# Board_Tanggal_v2.net
KiCad netlist of a schematic drawn in EAGLE
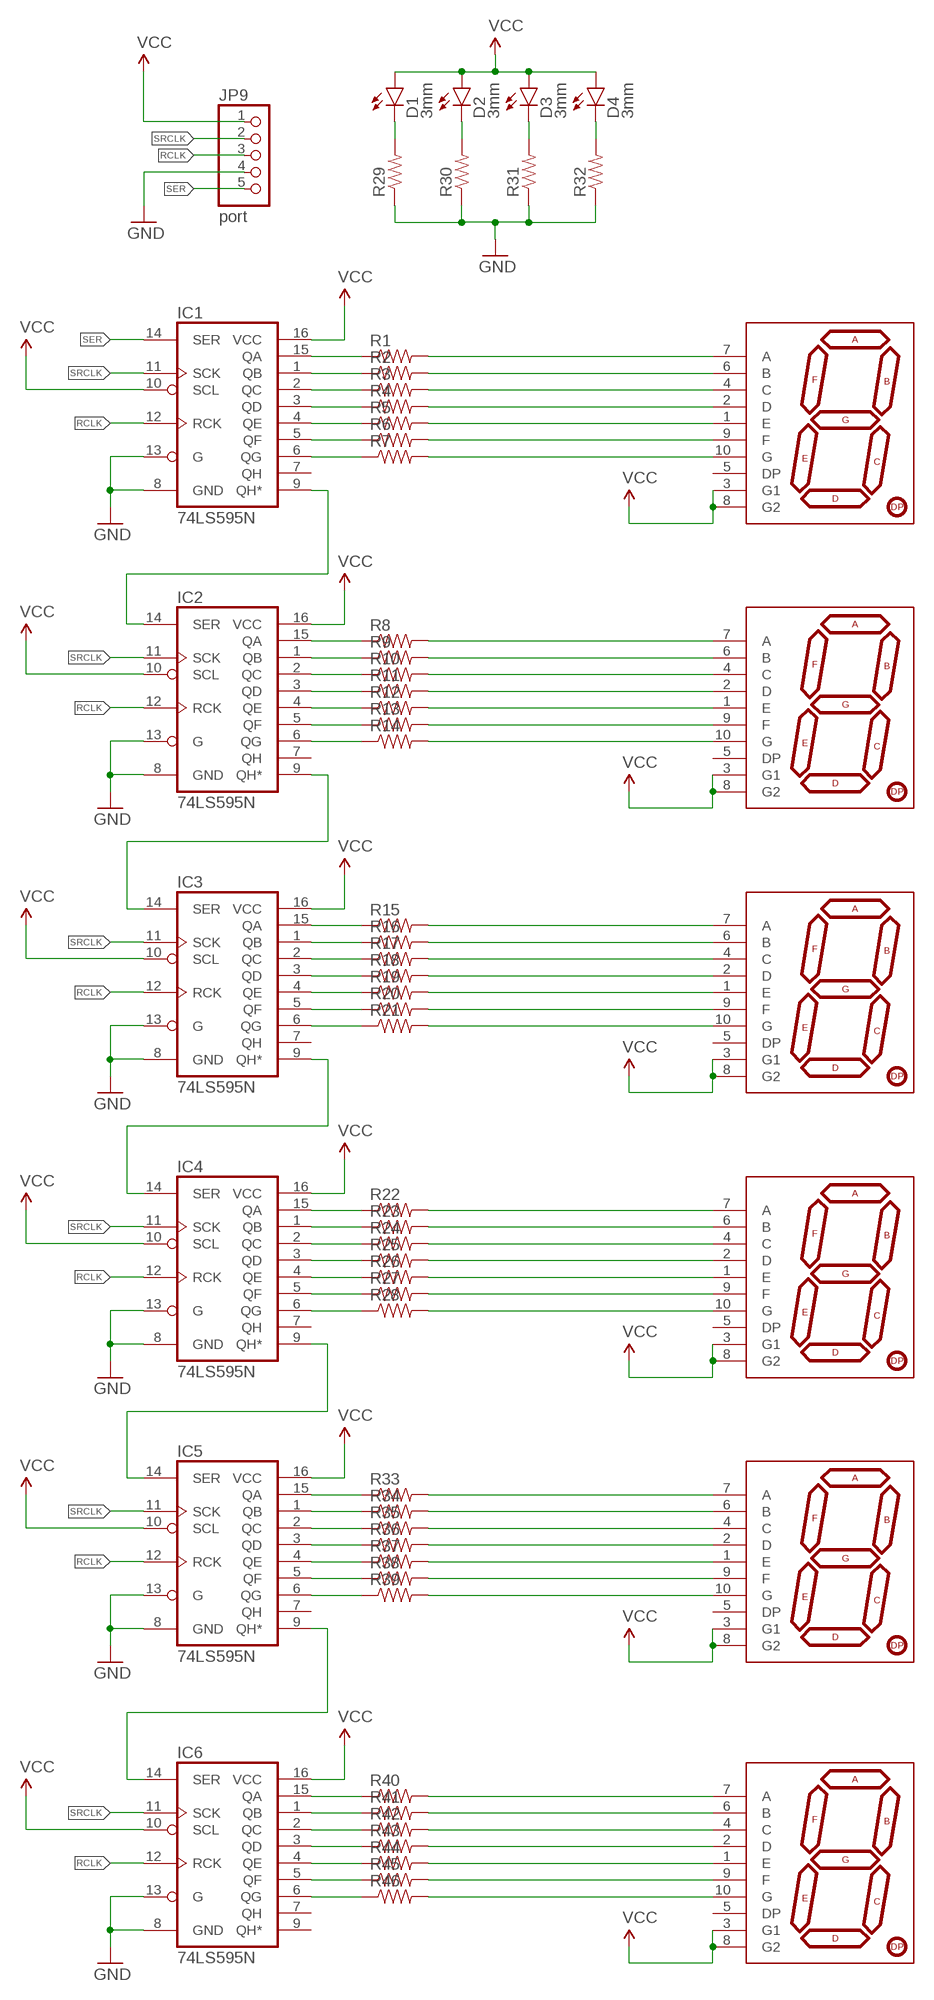
[diagram p0: schematic, sheet 1]

(export (version "E")
  (design (tool "Eeschema 10.0.6"))
  (components
    (comp (ref "D1")
      (value "3mm")
      (footprint "eagle-import:LED3MM")
      (libsource (lib "eagle-import") (part "LED3MM"))
    )
    (comp (ref "D2")
      (value "3mm")
      (footprint "eagle-import:LED3MM")
      (libsource (lib "eagle-import") (part "LED3MM"))
    )
    (comp (ref "D3")
      (value "3mm")
      (footprint "eagle-import:LED3MM")
      (libsource (lib "eagle-import") (part "LED3MM"))
    )
    (comp (ref "D4")
      (value "3mm")
      (footprint "eagle-import:LED3MM")
      (libsource (lib "eagle-import") (part "LED3MM"))
    )
    (comp (ref "IC1")
      (value "74LS595N")
      (footprint "eagle-import:DIL16")
      (libsource (lib "eagle-import") (part "74595NLS"))
    )
    (comp (ref "IC2")
      (value "74LS595N")
      (footprint "eagle-import:DIL16")
      (libsource (lib "eagle-import") (part "74595NLS"))
    )
    (comp (ref "IC3")
      (value "74LS595N")
      (footprint "eagle-import:DIL16")
      (libsource (lib "eagle-import") (part "74595NLS"))
    )
    (comp (ref "IC4")
      (value "74LS595N")
      (footprint "eagle-import:DIL16")
      (libsource (lib "eagle-import") (part "74595NLS"))
    )
    (comp (ref "IC5")
      (value "74LS595N")
      (footprint "eagle-import:DIL16")
      (libsource (lib "eagle-import") (part "74595NLS"))
    )
    (comp (ref "IC6")
      (value "74LS595N")
      (footprint "eagle-import:DIL16")
      (libsource (lib "eagle-import") (part "74595NLS"))
    )
    (comp (ref "JP9")
      (value "port")
      (footprint "eagle-import:1X05")
      (libsource (lib "eagle-import") (part "PINHD-1X5"))
    )
    (comp (ref "R1")
      (value "RESISTORPTH-1/4W")
      (footprint "eagle-import:AXIAL-0.4")
      (libsource (lib "eagle-import") (part "RESISTORPTH-1/4W"))
    )
    (comp (ref "R2")
      (value "RESISTORPTH-1/4W")
      (footprint "eagle-import:AXIAL-0.4")
      (libsource (lib "eagle-import") (part "RESISTORPTH-1/4W"))
    )
    (comp (ref "R3")
      (value "RESISTORPTH-1/4W")
      (footprint "eagle-import:AXIAL-0.4")
      (libsource (lib "eagle-import") (part "RESISTORPTH-1/4W"))
    )
    (comp (ref "R4")
      (value "RESISTORPTH-1/4W")
      (footprint "eagle-import:AXIAL-0.4")
      (libsource (lib "eagle-import") (part "RESISTORPTH-1/4W"))
    )
    (comp (ref "R5")
      (value "RESISTORPTH-1/4W")
      (footprint "eagle-import:AXIAL-0.4")
      (libsource (lib "eagle-import") (part "RESISTORPTH-1/4W"))
    )
    (comp (ref "R6")
      (value "RESISTORPTH-1/4W")
      (footprint "eagle-import:AXIAL-0.4")
      (libsource (lib "eagle-import") (part "RESISTORPTH-1/4W"))
    )
    (comp (ref "R7")
      (value "RESISTORPTH-1/4W")
      (footprint "eagle-import:AXIAL-0.4")
      (libsource (lib "eagle-import") (part "RESISTORPTH-1/4W"))
    )
    (comp (ref "R8")
      (value "RESISTORPTH-1/4W")
      (footprint "eagle-import:AXIAL-0.4")
      (libsource (lib "eagle-import") (part "RESISTORPTH-1/4W"))
    )
    (comp (ref "R9")
      (value "RESISTORPTH-1/4W")
      (footprint "eagle-import:AXIAL-0.4")
      (libsource (lib "eagle-import") (part "RESISTORPTH-1/4W"))
    )
    (comp (ref "R10")
      (value "RESISTORPTH-1/4W")
      (footprint "eagle-import:AXIAL-0.4")
      (libsource (lib "eagle-import") (part "RESISTORPTH-1/4W"))
    )
    (comp (ref "R11")
      (value "RESISTORPTH-1/4W")
      (footprint "eagle-import:AXIAL-0.4")
      (libsource (lib "eagle-import") (part "RESISTORPTH-1/4W"))
    )
    (comp (ref "R12")
      (value "RESISTORPTH-1/4W")
      (footprint "eagle-import:AXIAL-0.4")
      (libsource (lib "eagle-import") (part "RESISTORPTH-1/4W"))
    )
    (comp (ref "R13")
      (value "RESISTORPTH-1/4W")
      (footprint "eagle-import:AXIAL-0.4")
      (libsource (lib "eagle-import") (part "RESISTORPTH-1/4W"))
    )
    (comp (ref "R14")
      (value "RESISTORPTH-1/4W")
      (footprint "eagle-import:AXIAL-0.4")
      (libsource (lib "eagle-import") (part "RESISTORPTH-1/4W"))
    )
    (comp (ref "R15")
      (value "RESISTORPTH-1/4W")
      (footprint "eagle-import:AXIAL-0.4")
      (libsource (lib "eagle-import") (part "RESISTORPTH-1/4W"))
    )
    (comp (ref "R16")
      (value "RESISTORPTH-1/4W")
      (footprint "eagle-import:AXIAL-0.4")
      (libsource (lib "eagle-import") (part "RESISTORPTH-1/4W"))
    )
    (comp (ref "R17")
      (value "RESISTORPTH-1/4W")
      (footprint "eagle-import:AXIAL-0.4")
      (libsource (lib "eagle-import") (part "RESISTORPTH-1/4W"))
    )
    (comp (ref "R18")
      (value "RESISTORPTH-1/4W")
      (footprint "eagle-import:AXIAL-0.4")
      (libsource (lib "eagle-import") (part "RESISTORPTH-1/4W"))
    )
    (comp (ref "R19")
      (value "RESISTORPTH-1/4W")
      (footprint "eagle-import:AXIAL-0.4")
      (libsource (lib "eagle-import") (part "RESISTORPTH-1/4W"))
    )
    (comp (ref "R20")
      (value "RESISTORPTH-1/4W")
      (footprint "eagle-import:AXIAL-0.4")
      (libsource (lib "eagle-import") (part "RESISTORPTH-1/4W"))
    )
    (comp (ref "R21")
      (value "RESISTORPTH-1/4W")
      (footprint "eagle-import:AXIAL-0.4")
      (libsource (lib "eagle-import") (part "RESISTORPTH-1/4W"))
    )
    (comp (ref "R22")
      (value "RESISTORPTH-1/4W")
      (footprint "eagle-import:AXIAL-0.4")
      (libsource (lib "eagle-import") (part "RESISTORPTH-1/4W"))
    )
    (comp (ref "R23")
      (value "RESISTORPTH-1/4W")
      (footprint "eagle-import:AXIAL-0.4")
      (libsource (lib "eagle-import") (part "RESISTORPTH-1/4W"))
    )
    (comp (ref "R24")
      (value "RESISTORPTH-1/4W")
      (footprint "eagle-import:AXIAL-0.4")
      (libsource (lib "eagle-import") (part "RESISTORPTH-1/4W"))
    )
    (comp (ref "R25")
      (value "RESISTORPTH-1/4W")
      (footprint "eagle-import:AXIAL-0.4")
      (libsource (lib "eagle-import") (part "RESISTORPTH-1/4W"))
    )
    (comp (ref "R26")
      (value "RESISTORPTH-1/4W")
      (footprint "eagle-import:AXIAL-0.4")
      (libsource (lib "eagle-import") (part "RESISTORPTH-1/4W"))
    )
    (comp (ref "R27")
      (value "RESISTORPTH-1/4W")
      (footprint "eagle-import:AXIAL-0.4")
      (libsource (lib "eagle-import") (part "RESISTORPTH-1/4W"))
    )
    (comp (ref "R28")
      (value "RESISTORPTH-1/4W")
      (footprint "eagle-import:AXIAL-0.4")
      (libsource (lib "eagle-import") (part "RESISTORPTH-1/4W"))
    )
    (comp (ref "R29")
      (value "RESISTORPTH-1/4W")
      (footprint "eagle-import:AXIAL-0.4")
      (libsource (lib "eagle-import") (part "RESISTORPTH-1/4W"))
    )
    (comp (ref "R30")
      (value "RESISTORPTH-1/4W")
      (footprint "eagle-import:AXIAL-0.4")
      (libsource (lib "eagle-import") (part "RESISTORPTH-1/4W"))
    )
    (comp (ref "R31")
      (value "RESISTORPTH-1/4W")
      (footprint "eagle-import:AXIAL-0.4")
      (libsource (lib "eagle-import") (part "RESISTORPTH-1/4W"))
    )
    (comp (ref "R32")
      (value "RESISTORPTH-1/4W")
      (footprint "eagle-import:AXIAL-0.4")
      (libsource (lib "eagle-import") (part "RESISTORPTH-1/4W"))
    )
    (comp (ref "R33")
      (value "RESISTORPTH-1/4W")
      (footprint "eagle-import:AXIAL-0.4")
      (libsource (lib "eagle-import") (part "RESISTORPTH-1/4W"))
    )
    (comp (ref "R34")
      (value "RESISTORPTH-1/4W")
      (footprint "eagle-import:AXIAL-0.4")
      (libsource (lib "eagle-import") (part "RESISTORPTH-1/4W"))
    )
    (comp (ref "R35")
      (value "RESISTORPTH-1/4W")
      (footprint "eagle-import:AXIAL-0.4")
      (libsource (lib "eagle-import") (part "RESISTORPTH-1/4W"))
    )
    (comp (ref "R36")
      (value "RESISTORPTH-1/4W")
      (footprint "eagle-import:AXIAL-0.4")
      (libsource (lib "eagle-import") (part "RESISTORPTH-1/4W"))
    )
    (comp (ref "R37")
      (value "RESISTORPTH-1/4W")
      (footprint "eagle-import:AXIAL-0.4")
      (libsource (lib "eagle-import") (part "RESISTORPTH-1/4W"))
    )
    (comp (ref "R38")
      (value "RESISTORPTH-1/4W")
      (footprint "eagle-import:AXIAL-0.4")
      (libsource (lib "eagle-import") (part "RESISTORPTH-1/4W"))
    )
    (comp (ref "R39")
      (value "RESISTORPTH-1/4W")
      (footprint "eagle-import:AXIAL-0.4")
      (libsource (lib "eagle-import") (part "RESISTORPTH-1/4W"))
    )
    (comp (ref "R40")
      (value "RESISTORPTH-1/4W")
      (footprint "eagle-import:AXIAL-0.4")
      (libsource (lib "eagle-import") (part "RESISTORPTH-1/4W"))
    )
    (comp (ref "R41")
      (value "RESISTORPTH-1/4W")
      (footprint "eagle-import:AXIAL-0.4")
      (libsource (lib "eagle-import") (part "RESISTORPTH-1/4W"))
    )
    (comp (ref "R42")
      (value "RESISTORPTH-1/4W")
      (footprint "eagle-import:AXIAL-0.4")
      (libsource (lib "eagle-import") (part "RESISTORPTH-1/4W"))
    )
    (comp (ref "R43")
      (value "RESISTORPTH-1/4W")
      (footprint "eagle-import:AXIAL-0.4")
      (libsource (lib "eagle-import") (part "RESISTORPTH-1/4W"))
    )
    (comp (ref "R44")
      (value "RESISTORPTH-1/4W")
      (footprint "eagle-import:AXIAL-0.4")
      (libsource (lib "eagle-import") (part "RESISTORPTH-1/4W"))
    )
    (comp (ref "R45")
      (value "RESISTORPTH-1/4W")
      (footprint "eagle-import:AXIAL-0.4")
      (libsource (lib "eagle-import") (part "RESISTORPTH-1/4W"))
    )
    (comp (ref "R46")
      (value "RESISTORPTH-1/4W")
      (footprint "eagle-import:AXIAL-0.4")
      (libsource (lib "eagle-import") (part "RESISTORPTH-1/4W"))
    )
    (comp (ref "U$1")
      (value "7-SEGMENT-DISPLAY-1\"-REDEZ")
      (footprint "eagle-import:7-SEGMENT-1_PTH-EZ")
      (libsource (lib "eagle-import") (part "7-SEGMENT-DISPLAY-1{dblquote}-REDEZ"))
    )
    (comp (ref "U$2")
      (value "7-SEGMENT-DISPLAY-1\"-REDEZ")
      (footprint "eagle-import:7-SEGMENT-1_PTH-EZ")
      (libsource (lib "eagle-import") (part "7-SEGMENT-DISPLAY-1{dblquote}-REDEZ"))
    )
    (comp (ref "U$3")
      (value "7-SEGMENT-DISPLAY-1\"-REDEZ")
      (footprint "eagle-import:7-SEGMENT-1_PTH-EZ")
      (libsource (lib "eagle-import") (part "7-SEGMENT-DISPLAY-1{dblquote}-REDEZ"))
    )
    (comp (ref "U$4")
      (value "7-SEGMENT-DISPLAY-1\"-REDEZ")
      (footprint "eagle-import:7-SEGMENT-1_PTH-EZ")
      (libsource (lib "eagle-import") (part "7-SEGMENT-DISPLAY-1{dblquote}-REDEZ"))
    )
    (comp (ref "U$5")
      (value "7-SEGMENT-DISPLAY-1\"-REDEZ")
      (footprint "eagle-import:7-SEGMENT-1_PTH-EZ")
      (libsource (lib "eagle-import") (part "7-SEGMENT-DISPLAY-1{dblquote}-REDEZ"))
    )
    (comp (ref "U$6")
      (value "7-SEGMENT-DISPLAY-1\"-REDEZ")
      (footprint "eagle-import:7-SEGMENT-1_PTH-EZ")
      (libsource (lib "eagle-import") (part "7-SEGMENT-DISPLAY-1{dblquote}-REDEZ"))
    )
  )
  (nets
    (net (code "1") (name "GND") (class "Default")
      (node (ref "IC1") (pin "13") (pinfunction "G_13") (pintype "input"))
      (node (ref "IC1") (pin "8") (pinfunction "GND_8") (pintype "power_in"))
      (node (ref "IC2") (pin "13") (pinfunction "G_13") (pintype "input"))
      (node (ref "IC2") (pin "8") (pinfunction "GND_8") (pintype "power_in"))
      (node (ref "IC3") (pin "13") (pinfunction "G_13") (pintype "input"))
      (node (ref "IC3") (pin "8") (pinfunction "GND_8") (pintype "power_in"))
      (node (ref "IC4") (pin "13") (pinfunction "G_13") (pintype "input"))
      (node (ref "IC4") (pin "8") (pinfunction "GND_8") (pintype "power_in"))
      (node (ref "IC5") (pin "13") (pinfunction "G_13") (pintype "input"))
      (node (ref "IC5") (pin "8") (pinfunction "GND_8") (pintype "power_in"))
      (node (ref "IC6") (pin "13") (pinfunction "G_13") (pintype "input"))
      (node (ref "IC6") (pin "8") (pinfunction "GND_8") (pintype "power_in"))
      (node (ref "JP9") (pin "4") (pinfunction "4_4") (pintype "passive"))
      (node (ref "R29") (pin "P$1") (pinfunction "1_P$1") (pintype "passive"))
      (node (ref "R30") (pin "P$1") (pinfunction "1_P$1") (pintype "passive"))
      (node (ref "R31") (pin "P$1") (pinfunction "1_P$1") (pintype "passive"))
      (node (ref "R32") (pin "P$1") (pinfunction "1_P$1") (pintype "passive"))
    )
    (net (code "2") (name "Net-(D1-C)") (class "Default")
      (node (ref "D1") (pin "K") (pinfunction "C_K") (pintype "passive"))
      (node (ref "R29") (pin "P$2") (pinfunction "2_P$2") (pintype "passive"))
    )
    (net (code "3") (name "Net-(D2-C)") (class "Default")
      (node (ref "D2") (pin "K") (pinfunction "C_K") (pintype "passive"))
      (node (ref "R30") (pin "P$2") (pinfunction "2_P$2") (pintype "passive"))
    )
    (net (code "4") (name "Net-(D3-C)") (class "Default")
      (node (ref "D3") (pin "K") (pinfunction "C_K") (pintype "passive"))
      (node (ref "R31") (pin "P$2") (pinfunction "2_P$2") (pintype "passive"))
    )
    (net (code "5") (name "Net-(D4-C)") (class "Default")
      (node (ref "D4") (pin "K") (pinfunction "C_K") (pintype "passive"))
      (node (ref "R32") (pin "P$2") (pinfunction "2_P$2") (pintype "passive"))
    )
    (net (code "6") (name "Net-(IC1-QA)") (class "Default")
      (node (ref "IC1") (pin "15") (pinfunction "QA_15") (pintype "tri_state"))
      (node (ref "R1") (pin "P$1") (pinfunction "1_P$1") (pintype "passive"))
    )
    (net (code "7") (name "Net-(IC1-QB)") (class "Default")
      (node (ref "IC1") (pin "1") (pinfunction "QB_1") (pintype "tri_state"))
      (node (ref "R2") (pin "P$1") (pinfunction "1_P$1") (pintype "passive"))
    )
    (net (code "8") (name "Net-(IC1-QC)") (class "Default")
      (node (ref "IC1") (pin "2") (pinfunction "QC_2") (pintype "tri_state"))
      (node (ref "R3") (pin "P$1") (pinfunction "1_P$1") (pintype "passive"))
    )
    (net (code "9") (name "Net-(IC1-QD)") (class "Default")
      (node (ref "IC1") (pin "3") (pinfunction "QD_3") (pintype "tri_state"))
      (node (ref "R4") (pin "P$1") (pinfunction "1_P$1") (pintype "passive"))
    )
    (net (code "10") (name "Net-(IC1-QE)") (class "Default")
      (node (ref "IC1") (pin "4") (pinfunction "QE_4") (pintype "tri_state"))
      (node (ref "R5") (pin "P$1") (pinfunction "1_P$1") (pintype "passive"))
    )
    (net (code "11") (name "Net-(IC1-QF)") (class "Default")
      (node (ref "IC1") (pin "5") (pinfunction "QF_5") (pintype "tri_state"))
      (node (ref "R6") (pin "P$1") (pinfunction "1_P$1") (pintype "passive"))
    )
    (net (code "12") (name "Net-(IC1-QG)") (class "Default")
      (node (ref "IC1") (pin "6") (pinfunction "QG_6") (pintype "tri_state"))
      (node (ref "R7") (pin "P$1") (pinfunction "1_P$1") (pintype "passive"))
    )
    (net (code "13") (name "Net-(IC1-QH*)") (class "Default")
      (node (ref "IC1") (pin "9") (pinfunction "QH*_9") (pintype "tri_state"))
      (node (ref "IC2") (pin "14") (pinfunction "SER_14") (pintype "input"))
    )
    (net (code "14") (name "Net-(IC2-QA)") (class "Default")
      (node (ref "IC2") (pin "15") (pinfunction "QA_15") (pintype "tri_state"))
      (node (ref "R8") (pin "P$1") (pinfunction "1_P$1") (pintype "passive"))
    )
    (net (code "15") (name "Net-(IC2-QB)") (class "Default")
      (node (ref "IC2") (pin "1") (pinfunction "QB_1") (pintype "tri_state"))
      (node (ref "R9") (pin "P$1") (pinfunction "1_P$1") (pintype "passive"))
    )
    (net (code "16") (name "Net-(IC2-QC)") (class "Default")
      (node (ref "IC2") (pin "2") (pinfunction "QC_2") (pintype "tri_state"))
      (node (ref "R10") (pin "P$1") (pinfunction "1_P$1") (pintype "passive"))
    )
    (net (code "17") (name "Net-(IC2-QD)") (class "Default")
      (node (ref "IC2") (pin "3") (pinfunction "QD_3") (pintype "tri_state"))
      (node (ref "R11") (pin "P$1") (pinfunction "1_P$1") (pintype "passive"))
    )
    (net (code "18") (name "Net-(IC2-QE)") (class "Default")
      (node (ref "IC2") (pin "4") (pinfunction "QE_4") (pintype "tri_state"))
      (node (ref "R12") (pin "P$1") (pinfunction "1_P$1") (pintype "passive"))
    )
    (net (code "19") (name "Net-(IC2-QF)") (class "Default")
      (node (ref "IC2") (pin "5") (pinfunction "QF_5") (pintype "tri_state"))
      (node (ref "R13") (pin "P$1") (pinfunction "1_P$1") (pintype "passive"))
    )
    (net (code "20") (name "Net-(IC2-QG)") (class "Default")
      (node (ref "IC2") (pin "6") (pinfunction "QG_6") (pintype "tri_state"))
      (node (ref "R14") (pin "P$1") (pinfunction "1_P$1") (pintype "passive"))
    )
    (net (code "21") (name "Net-(IC2-QH*)") (class "Default")
      (node (ref "IC2") (pin "9") (pinfunction "QH*_9") (pintype "tri_state"))
      (node (ref "IC3") (pin "14") (pinfunction "SER_14") (pintype "input"))
    )
    (net (code "22") (name "Net-(IC3-QA)") (class "Default")
      (node (ref "IC3") (pin "15") (pinfunction "QA_15") (pintype "tri_state"))
      (node (ref "R15") (pin "P$1") (pinfunction "1_P$1") (pintype "passive"))
    )
    (net (code "23") (name "Net-(IC3-QB)") (class "Default")
      (node (ref "IC3") (pin "1") (pinfunction "QB_1") (pintype "tri_state"))
      (node (ref "R16") (pin "P$1") (pinfunction "1_P$1") (pintype "passive"))
    )
    (net (code "24") (name "Net-(IC3-QC)") (class "Default")
      (node (ref "IC3") (pin "2") (pinfunction "QC_2") (pintype "tri_state"))
      (node (ref "R17") (pin "P$1") (pinfunction "1_P$1") (pintype "passive"))
    )
    (net (code "25") (name "Net-(IC3-QD)") (class "Default")
      (node (ref "IC3") (pin "3") (pinfunction "QD_3") (pintype "tri_state"))
      (node (ref "R18") (pin "P$1") (pinfunction "1_P$1") (pintype "passive"))
    )
    (net (code "26") (name "Net-(IC3-QE)") (class "Default")
      (node (ref "IC3") (pin "4") (pinfunction "QE_4") (pintype "tri_state"))
      (node (ref "R19") (pin "P$1") (pinfunction "1_P$1") (pintype "passive"))
    )
    (net (code "27") (name "Net-(IC3-QF)") (class "Default")
      (node (ref "IC3") (pin "5") (pinfunction "QF_5") (pintype "tri_state"))
      (node (ref "R20") (pin "P$1") (pinfunction "1_P$1") (pintype "passive"))
    )
    (net (code "28") (name "Net-(IC3-QG)") (class "Default")
      (node (ref "IC3") (pin "6") (pinfunction "QG_6") (pintype "tri_state"))
      (node (ref "R21") (pin "P$1") (pinfunction "1_P$1") (pintype "passive"))
    )
    (net (code "29") (name "Net-(IC3-QH*)") (class "Default")
      (node (ref "IC3") (pin "9") (pinfunction "QH*_9") (pintype "tri_state"))
      (node (ref "IC4") (pin "14") (pinfunction "SER_14") (pintype "input"))
    )
    (net (code "30") (name "Net-(IC4-QA)") (class "Default")
      (node (ref "IC4") (pin "15") (pinfunction "QA_15") (pintype "tri_state"))
      (node (ref "R22") (pin "P$1") (pinfunction "1_P$1") (pintype "passive"))
    )
    (net (code "31") (name "Net-(IC4-QB)") (class "Default")
      (node (ref "IC4") (pin "1") (pinfunction "QB_1") (pintype "tri_state"))
      (node (ref "R23") (pin "P$1") (pinfunction "1_P$1") (pintype "passive"))
    )
    (net (code "32") (name "Net-(IC4-QC)") (class "Default")
      (node (ref "IC4") (pin "2") (pinfunction "QC_2") (pintype "tri_state"))
      (node (ref "R24") (pin "P$1") (pinfunction "1_P$1") (pintype "passive"))
    )
    (net (code "33") (name "Net-(IC4-QD)") (class "Default")
      (node (ref "IC4") (pin "3") (pinfunction "QD_3") (pintype "tri_state"))
      (node (ref "R25") (pin "P$1") (pinfunction "1_P$1") (pintype "passive"))
    )
    (net (code "34") (name "Net-(IC4-QE)") (class "Default")
      (node (ref "IC4") (pin "4") (pinfunction "QE_4") (pintype "tri_state"))
      (node (ref "R26") (pin "P$1") (pinfunction "1_P$1") (pintype "passive"))
    )
    (net (code "35") (name "Net-(IC4-QF)") (class "Default")
      (node (ref "IC4") (pin "5") (pinfunction "QF_5") (pintype "tri_state"))
      (node (ref "R27") (pin "P$1") (pinfunction "1_P$1") (pintype "passive"))
    )
    (net (code "36") (name "Net-(IC4-QG)") (class "Default")
      (node (ref "IC4") (pin "6") (pinfunction "QG_6") (pintype "tri_state"))
      (node (ref "R28") (pin "P$1") (pinfunction "1_P$1") (pintype "passive"))
    )
    (net (code "37") (name "Net-(IC4-QH*)") (class "Default")
      (node (ref "IC4") (pin "9") (pinfunction "QH*_9") (pintype "tri_state"))
      (node (ref "IC5") (pin "14") (pinfunction "SER_14") (pintype "input"))
    )
    (net (code "38") (name "Net-(IC5-QA)") (class "Default")
      (node (ref "IC5") (pin "15") (pinfunction "QA_15") (pintype "tri_state"))
      (node (ref "R33") (pin "P$1") (pinfunction "1_P$1") (pintype "passive"))
    )
    (net (code "39") (name "Net-(IC5-QB)") (class "Default")
      (node (ref "IC5") (pin "1") (pinfunction "QB_1") (pintype "tri_state"))
      (node (ref "R34") (pin "P$1") (pinfunction "1_P$1") (pintype "passive"))
    )
    (net (code "40") (name "Net-(IC5-QC)") (class "Default")
      (node (ref "IC5") (pin "2") (pinfunction "QC_2") (pintype "tri_state"))
      (node (ref "R35") (pin "P$1") (pinfunction "1_P$1") (pintype "passive"))
    )
    (net (code "41") (name "Net-(IC5-QD)") (class "Default")
      (node (ref "IC5") (pin "3") (pinfunction "QD_3") (pintype "tri_state"))
      (node (ref "R36") (pin "P$1") (pinfunction "1_P$1") (pintype "passive"))
    )
    (net (code "42") (name "Net-(IC5-QE)") (class "Default")
      (node (ref "IC5") (pin "4") (pinfunction "QE_4") (pintype "tri_state"))
      (node (ref "R37") (pin "P$1") (pinfunction "1_P$1") (pintype "passive"))
    )
    (net (code "43") (name "Net-(IC5-QF)") (class "Default")
      (node (ref "IC5") (pin "5") (pinfunction "QF_5") (pintype "tri_state"))
      (node (ref "R38") (pin "P$1") (pinfunction "1_P$1") (pintype "passive"))
    )
    (net (code "44") (name "Net-(IC5-QG)") (class "Default")
      (node (ref "IC5") (pin "6") (pinfunction "QG_6") (pintype "tri_state"))
      (node (ref "R39") (pin "P$1") (pinfunction "1_P$1") (pintype "passive"))
    )
    (net (code "45") (name "Net-(IC5-QH*)") (class "Default")
      (node (ref "IC5") (pin "9") (pinfunction "QH*_9") (pintype "tri_state"))
      (node (ref "IC6") (pin "14") (pinfunction "SER_14") (pintype "input"))
    )
    (net (code "46") (name "Net-(IC6-QA)") (class "Default")
      (node (ref "IC6") (pin "15") (pinfunction "QA_15") (pintype "tri_state"))
      (node (ref "R40") (pin "P$1") (pinfunction "1_P$1") (pintype "passive"))
    )
    (net (code "47") (name "Net-(IC6-QB)") (class "Default")
      (node (ref "IC6") (pin "1") (pinfunction "QB_1") (pintype "tri_state"))
      (node (ref "R41") (pin "P$1") (pinfunction "1_P$1") (pintype "passive"))
    )
    (net (code "48") (name "Net-(IC6-QC)") (class "Default")
      (node (ref "IC6") (pin "2") (pinfunction "QC_2") (pintype "tri_state"))
      (node (ref "R42") (pin "P$1") (pinfunction "1_P$1") (pintype "passive"))
    )
    (net (code "49") (name "Net-(IC6-QD)") (class "Default")
      (node (ref "IC6") (pin "3") (pinfunction "QD_3") (pintype "tri_state"))
      (node (ref "R43") (pin "P$1") (pinfunction "1_P$1") (pintype "passive"))
    )
    (net (code "50") (name "Net-(IC6-QE)") (class "Default")
      (node (ref "IC6") (pin "4") (pinfunction "QE_4") (pintype "tri_state"))
      (node (ref "R44") (pin "P$1") (pinfunction "1_P$1") (pintype "passive"))
    )
    (net (code "51") (name "Net-(IC6-QF)") (class "Default")
      (node (ref "IC6") (pin "5") (pinfunction "QF_5") (pintype "tri_state"))
      (node (ref "R45") (pin "P$1") (pinfunction "1_P$1") (pintype "passive"))
    )
    (net (code "52") (name "Net-(IC6-QG)") (class "Default")
      (node (ref "IC6") (pin "6") (pinfunction "QG_6") (pintype "tri_state"))
      (node (ref "R46") (pin "P$1") (pinfunction "1_P$1") (pintype "passive"))
    )
    (net (code "53") (name "Net-(R1-2)") (class "Default")
      (node (ref "R1") (pin "P$2") (pinfunction "2_P$2") (pintype "passive"))
      (node (ref "U$1") (pin "7") (pinfunction "A_7") (pintype "bidirectional"))
    )
    (net (code "54") (name "Net-(R2-2)") (class "Default")
      (node (ref "R2") (pin "P$2") (pinfunction "2_P$2") (pintype "passive"))
      (node (ref "U$1") (pin "6") (pinfunction "B_6") (pintype "bidirectional"))
    )
    (net (code "55") (name "Net-(R3-2)") (class "Default")
      (node (ref "R3") (pin "P$2") (pinfunction "2_P$2") (pintype "passive"))
      (node (ref "U$1") (pin "4") (pinfunction "C_4") (pintype "bidirectional"))
    )
    (net (code "56") (name "Net-(R4-2)") (class "Default")
      (node (ref "R4") (pin "P$2") (pinfunction "2_P$2") (pintype "passive"))
      (node (ref "U$1") (pin "2") (pinfunction "D_2") (pintype "bidirectional"))
    )
    (net (code "57") (name "Net-(R5-2)") (class "Default")
      (node (ref "R5") (pin "P$2") (pinfunction "2_P$2") (pintype "passive"))
      (node (ref "U$1") (pin "1") (pinfunction "E_1") (pintype "bidirectional"))
    )
    (net (code "58") (name "Net-(R6-2)") (class "Default")
      (node (ref "R6") (pin "P$2") (pinfunction "2_P$2") (pintype "passive"))
      (node (ref "U$1") (pin "9") (pinfunction "F_9") (pintype "bidirectional"))
    )
    (net (code "59") (name "Net-(R7-2)") (class "Default")
      (node (ref "R7") (pin "P$2") (pinfunction "2_P$2") (pintype "passive"))
      (node (ref "U$1") (pin "10") (pinfunction "G_10") (pintype "bidirectional"))
    )
    (net (code "60") (name "Net-(R8-2)") (class "Default")
      (node (ref "R8") (pin "P$2") (pinfunction "2_P$2") (pintype "passive"))
      (node (ref "U$2") (pin "7") (pinfunction "A_7") (pintype "bidirectional"))
    )
    (net (code "61") (name "Net-(R9-2)") (class "Default")
      (node (ref "R9") (pin "P$2") (pinfunction "2_P$2") (pintype "passive"))
      (node (ref "U$2") (pin "6") (pinfunction "B_6") (pintype "bidirectional"))
    )
    (net (code "62") (name "Net-(R10-2)") (class "Default")
      (node (ref "R10") (pin "P$2") (pinfunction "2_P$2") (pintype "passive"))
      (node (ref "U$2") (pin "4") (pinfunction "C_4") (pintype "bidirectional"))
    )
    (net (code "63") (name "Net-(R11-2)") (class "Default")
      (node (ref "R11") (pin "P$2") (pinfunction "2_P$2") (pintype "passive"))
      (node (ref "U$2") (pin "2") (pinfunction "D_2") (pintype "bidirectional"))
    )
    (net (code "64") (name "Net-(R12-2)") (class "Default")
      (node (ref "R12") (pin "P$2") (pinfunction "2_P$2") (pintype "passive"))
      (node (ref "U$2") (pin "1") (pinfunction "E_1") (pintype "bidirectional"))
    )
    (net (code "65") (name "Net-(R13-2)") (class "Default")
      (node (ref "R13") (pin "P$2") (pinfunction "2_P$2") (pintype "passive"))
      (node (ref "U$2") (pin "9") (pinfunction "F_9") (pintype "bidirectional"))
    )
    (net (code "66") (name "Net-(R14-2)") (class "Default")
      (node (ref "R14") (pin "P$2") (pinfunction "2_P$2") (pintype "passive"))
      (node (ref "U$2") (pin "10") (pinfunction "G_10") (pintype "bidirectional"))
    )
    (net (code "67") (name "Net-(R15-2)") (class "Default")
      (node (ref "R15") (pin "P$2") (pinfunction "2_P$2") (pintype "passive"))
      (node (ref "U$3") (pin "7") (pinfunction "A_7") (pintype "bidirectional"))
    )
    (net (code "68") (name "Net-(R16-2)") (class "Default")
      (node (ref "R16") (pin "P$2") (pinfunction "2_P$2") (pintype "passive"))
      (node (ref "U$3") (pin "6") (pinfunction "B_6") (pintype "bidirectional"))
    )
    (net (code "69") (name "Net-(R17-2)") (class "Default")
      (node (ref "R17") (pin "P$2") (pinfunction "2_P$2") (pintype "passive"))
      (node (ref "U$3") (pin "4") (pinfunction "C_4") (pintype "bidirectional"))
    )
    (net (code "70") (name "Net-(R18-2)") (class "Default")
      (node (ref "R18") (pin "P$2") (pinfunction "2_P$2") (pintype "passive"))
      (node (ref "U$3") (pin "2") (pinfunction "D_2") (pintype "bidirectional"))
    )
    (net (code "71") (name "Net-(R19-2)") (class "Default")
      (node (ref "R19") (pin "P$2") (pinfunction "2_P$2") (pintype "passive"))
      (node (ref "U$3") (pin "1") (pinfunction "E_1") (pintype "bidirectional"))
    )
    (net (code "72") (name "Net-(R20-2)") (class "Default")
      (node (ref "R20") (pin "P$2") (pinfunction "2_P$2") (pintype "passive"))
      (node (ref "U$3") (pin "9") (pinfunction "F_9") (pintype "bidirectional"))
    )
    (net (code "73") (name "Net-(R21-2)") (class "Default")
      (node (ref "R21") (pin "P$2") (pinfunction "2_P$2") (pintype "passive"))
      (node (ref "U$3") (pin "10") (pinfunction "G_10") (pintype "bidirectional"))
    )
    (net (code "74") (name "Net-(R22-2)") (class "Default")
      (node (ref "R22") (pin "P$2") (pinfunction "2_P$2") (pintype "passive"))
      (node (ref "U$4") (pin "7") (pinfunction "A_7") (pintype "bidirectional"))
    )
    (net (code "75") (name "Net-(R23-2)") (class "Default")
      (node (ref "R23") (pin "P$2") (pinfunction "2_P$2") (pintype "passive"))
      (node (ref "U$4") (pin "6") (pinfunction "B_6") (pintype "bidirectional"))
    )
    (net (code "76") (name "Net-(R24-2)") (class "Default")
      (node (ref "R24") (pin "P$2") (pinfunction "2_P$2") (pintype "passive"))
      (node (ref "U$4") (pin "4") (pinfunction "C_4") (pintype "bidirectional"))
    )
    (net (code "77") (name "Net-(R25-2)") (class "Default")
      (node (ref "R25") (pin "P$2") (pinfunction "2_P$2") (pintype "passive"))
      (node (ref "U$4") (pin "2") (pinfunction "D_2") (pintype "bidirectional"))
    )
    (net (code "78") (name "Net-(R26-2)") (class "Default")
      (node (ref "R26") (pin "P$2") (pinfunction "2_P$2") (pintype "passive"))
      (node (ref "U$4") (pin "1") (pinfunction "E_1") (pintype "bidirectional"))
    )
    (net (code "79") (name "Net-(R27-2)") (class "Default")
      (node (ref "R27") (pin "P$2") (pinfunction "2_P$2") (pintype "passive"))
      (node (ref "U$4") (pin "9") (pinfunction "F_9") (pintype "bidirectional"))
    )
    (net (code "80") (name "Net-(R28-2)") (class "Default")
      (node (ref "R28") (pin "P$2") (pinfunction "2_P$2") (pintype "passive"))
      (node (ref "U$4") (pin "10") (pinfunction "G_10") (pintype "bidirectional"))
    )
    (net (code "81") (name "Net-(R33-2)") (class "Default")
      (node (ref "R33") (pin "P$2") (pinfunction "2_P$2") (pintype "passive"))
      (node (ref "U$5") (pin "7") (pinfunction "A_7") (pintype "bidirectional"))
    )
    (net (code "82") (name "Net-(R34-2)") (class "Default")
      (node (ref "R34") (pin "P$2") (pinfunction "2_P$2") (pintype "passive"))
      (node (ref "U$5") (pin "6") (pinfunction "B_6") (pintype "bidirectional"))
    )
    (net (code "83") (name "Net-(R35-2)") (class "Default")
      (node (ref "R35") (pin "P$2") (pinfunction "2_P$2") (pintype "passive"))
      (node (ref "U$5") (pin "4") (pinfunction "C_4") (pintype "bidirectional"))
    )
    (net (code "84") (name "Net-(R36-2)") (class "Default")
      (node (ref "R36") (pin "P$2") (pinfunction "2_P$2") (pintype "passive"))
      (node (ref "U$5") (pin "2") (pinfunction "D_2") (pintype "bidirectional"))
    )
    (net (code "85") (name "Net-(R37-2)") (class "Default")
      (node (ref "R37") (pin "P$2") (pinfunction "2_P$2") (pintype "passive"))
      (node (ref "U$5") (pin "1") (pinfunction "E_1") (pintype "bidirectional"))
    )
    (net (code "86") (name "Net-(R38-2)") (class "Default")
      (node (ref "R38") (pin "P$2") (pinfunction "2_P$2") (pintype "passive"))
      (node (ref "U$5") (pin "9") (pinfunction "F_9") (pintype "bidirectional"))
    )
    (net (code "87") (name "Net-(R39-2)") (class "Default")
      (node (ref "R39") (pin "P$2") (pinfunction "2_P$2") (pintype "passive"))
      (node (ref "U$5") (pin "10") (pinfunction "G_10") (pintype "bidirectional"))
    )
    (net (code "88") (name "Net-(R40-2)") (class "Default")
      (node (ref "R40") (pin "P$2") (pinfunction "2_P$2") (pintype "passive"))
      (node (ref "U$6") (pin "7") (pinfunction "A_7") (pintype "bidirectional"))
    )
    (net (code "89") (name "Net-(R41-2)") (class "Default")
      (node (ref "R41") (pin "P$2") (pinfunction "2_P$2") (pintype "passive"))
      (node (ref "U$6") (pin "6") (pinfunction "B_6") (pintype "bidirectional"))
    )
    (net (code "90") (name "Net-(R42-2)") (class "Default")
      (node (ref "R42") (pin "P$2") (pinfunction "2_P$2") (pintype "passive"))
      (node (ref "U$6") (pin "4") (pinfunction "C_4") (pintype "bidirectional"))
    )
    (net (code "91") (name "Net-(R43-2)") (class "Default")
      (node (ref "R43") (pin "P$2") (pinfunction "2_P$2") (pintype "passive"))
      (node (ref "U$6") (pin "2") (pinfunction "D_2") (pintype "bidirectional"))
    )
    (net (code "92") (name "Net-(R44-2)") (class "Default")
      (node (ref "R44") (pin "P$2") (pinfunction "2_P$2") (pintype "passive"))
      (node (ref "U$6") (pin "1") (pinfunction "E_1") (pintype "bidirectional"))
    )
    (net (code "93") (name "Net-(R45-2)") (class "Default")
      (node (ref "R45") (pin "P$2") (pinfunction "2_P$2") (pintype "passive"))
      (node (ref "U$6") (pin "9") (pinfunction "F_9") (pintype "bidirectional"))
    )
    (net (code "94") (name "Net-(R46-2)") (class "Default")
      (node (ref "R46") (pin "P$2") (pinfunction "2_P$2") (pintype "passive"))
      (node (ref "U$6") (pin "10") (pinfunction "G_10") (pintype "bidirectional"))
    )
    (net (code "95") (name "RCLK") (class "Default")
      (node (ref "IC1") (pin "12") (pinfunction "RCK_12") (pintype "input"))
      (node (ref "IC2") (pin "12") (pinfunction "RCK_12") (pintype "input"))
      (node (ref "IC3") (pin "12") (pinfunction "RCK_12") (pintype "input"))
      (node (ref "IC4") (pin "12") (pinfunction "RCK_12") (pintype "input"))
      (node (ref "IC5") (pin "12") (pinfunction "RCK_12") (pintype "input"))
      (node (ref "IC6") (pin "12") (pinfunction "RCK_12") (pintype "input"))
      (node (ref "JP9") (pin "3") (pinfunction "3_3") (pintype "passive"))
    )
    (net (code "96") (name "SER") (class "Default")
      (node (ref "IC1") (pin "14") (pinfunction "SER_14") (pintype "input"))
      (node (ref "JP9") (pin "5") (pinfunction "5_5") (pintype "passive"))
    )
    (net (code "97") (name "SRCLK") (class "Default")
      (node (ref "IC1") (pin "11") (pinfunction "SCK_11") (pintype "input"))
      (node (ref "IC2") (pin "11") (pinfunction "SCK_11") (pintype "input"))
      (node (ref "IC3") (pin "11") (pinfunction "SCK_11") (pintype "input"))
      (node (ref "IC4") (pin "11") (pinfunction "SCK_11") (pintype "input"))
      (node (ref "IC5") (pin "11") (pinfunction "SCK_11") (pintype "input"))
      (node (ref "IC6") (pin "11") (pinfunction "SCK_11") (pintype "input"))
      (node (ref "JP9") (pin "2") (pinfunction "2_2") (pintype "passive"))
    )
    (net (code "98") (name "VCC") (class "Default")
      (node (ref "D1") (pin "A") (pinfunction "A_A") (pintype "passive"))
      (node (ref "D2") (pin "A") (pinfunction "A_A") (pintype "passive"))
      (node (ref "D3") (pin "A") (pinfunction "A_A") (pintype "passive"))
      (node (ref "D4") (pin "A") (pinfunction "A_A") (pintype "passive"))
      (node (ref "IC1") (pin "10") (pinfunction "SCL_10") (pintype "input"))
      (node (ref "IC1") (pin "16") (pinfunction "VCC_16") (pintype "power_in"))
      (node (ref "IC2") (pin "10") (pinfunction "SCL_10") (pintype "input"))
      (node (ref "IC2") (pin "16") (pinfunction "VCC_16") (pintype "power_in"))
      (node (ref "IC3") (pin "10") (pinfunction "SCL_10") (pintype "input"))
      (node (ref "IC3") (pin "16") (pinfunction "VCC_16") (pintype "power_in"))
      (node (ref "IC4") (pin "10") (pinfunction "SCL_10") (pintype "input"))
      (node (ref "IC4") (pin "16") (pinfunction "VCC_16") (pintype "power_in"))
      (node (ref "IC5") (pin "10") (pinfunction "SCL_10") (pintype "input"))
      (node (ref "IC5") (pin "16") (pinfunction "VCC_16") (pintype "power_in"))
      (node (ref "IC6") (pin "10") (pinfunction "SCL_10") (pintype "input"))
      (node (ref "IC6") (pin "16") (pinfunction "VCC_16") (pintype "power_in"))
      (node (ref "JP9") (pin "1") (pinfunction "1_1") (pintype "passive"))
      (node (ref "U$1") (pin "3") (pinfunction "G1_3") (pintype "bidirectional"))
      (node (ref "U$1") (pin "8") (pinfunction "G2_8") (pintype "bidirectional"))
      (node (ref "U$2") (pin "3") (pinfunction "G1_3") (pintype "bidirectional"))
      (node (ref "U$2") (pin "8") (pinfunction "G2_8") (pintype "bidirectional"))
      (node (ref "U$3") (pin "3") (pinfunction "G1_3") (pintype "bidirectional"))
      (node (ref "U$3") (pin "8") (pinfunction "G2_8") (pintype "bidirectional"))
      (node (ref "U$4") (pin "3") (pinfunction "G1_3") (pintype "bidirectional"))
      (node (ref "U$4") (pin "8") (pinfunction "G2_8") (pintype "bidirectional"))
      (node (ref "U$5") (pin "3") (pinfunction "G1_3") (pintype "bidirectional"))
      (node (ref "U$5") (pin "8") (pinfunction "G2_8") (pintype "bidirectional"))
      (node (ref "U$6") (pin "3") (pinfunction "G1_3") (pintype "bidirectional"))
      (node (ref "U$6") (pin "8") (pinfunction "G2_8") (pintype "bidirectional"))
    )
    (net (code "99") (name "unconnected-(IC1-QH-Pad7)") (class "Default")
      (node (ref "IC1") (pin "7") (pinfunction "QH_7") (pintype "tri_state"))
    )
    (net (code "100") (name "unconnected-(IC2-QH-Pad7)") (class "Default")
      (node (ref "IC2") (pin "7") (pinfunction "QH_7") (pintype "tri_state"))
    )
    (net (code "101") (name "unconnected-(IC3-QH-Pad7)") (class "Default")
      (node (ref "IC3") (pin "7") (pinfunction "QH_7") (pintype "tri_state"))
    )
    (net (code "102") (name "unconnected-(IC4-QH-Pad7)") (class "Default")
      (node (ref "IC4") (pin "7") (pinfunction "QH_7") (pintype "tri_state"))
    )
    (net (code "103") (name "unconnected-(IC5-QH-Pad7)") (class "Default")
      (node (ref "IC5") (pin "7") (pinfunction "QH_7") (pintype "tri_state"))
    )
    (net (code "104") (name "unconnected-(IC6-QH*-Pad9)") (class "Default")
      (node (ref "IC6") (pin "9") (pinfunction "QH*_9") (pintype "tri_state"))
    )
    (net (code "105") (name "unconnected-(IC6-QH-Pad7)") (class "Default")
      (node (ref "IC6") (pin "7") (pinfunction "QH_7") (pintype "tri_state"))
    )
    (net (code "106") (name "unconnected-(U$1-DP-Pad5)") (class "Default")
      (node (ref "U$1") (pin "5") (pinfunction "DP_5") (pintype "bidirectional"))
    )
    (net (code "107") (name "unconnected-(U$2-DP-Pad5)") (class "Default")
      (node (ref "U$2") (pin "5") (pinfunction "DP_5") (pintype "bidirectional"))
    )
    (net (code "108") (name "unconnected-(U$3-DP-Pad5)") (class "Default")
      (node (ref "U$3") (pin "5") (pinfunction "DP_5") (pintype "bidirectional"))
    )
    (net (code "109") (name "unconnected-(U$4-DP-Pad5)") (class "Default")
      (node (ref "U$4") (pin "5") (pinfunction "DP_5") (pintype "bidirectional"))
    )
    (net (code "110") (name "unconnected-(U$5-DP-Pad5)") (class "Default")
      (node (ref "U$5") (pin "5") (pinfunction "DP_5") (pintype "bidirectional"))
    )
    (net (code "111") (name "unconnected-(U$6-DP-Pad5)") (class "Default")
      (node (ref "U$6") (pin "5") (pinfunction "DP_5") (pintype "bidirectional"))
    )
  )
)
